# amplifier.net
KiCad netlist of a schematic drawn in EAGLE
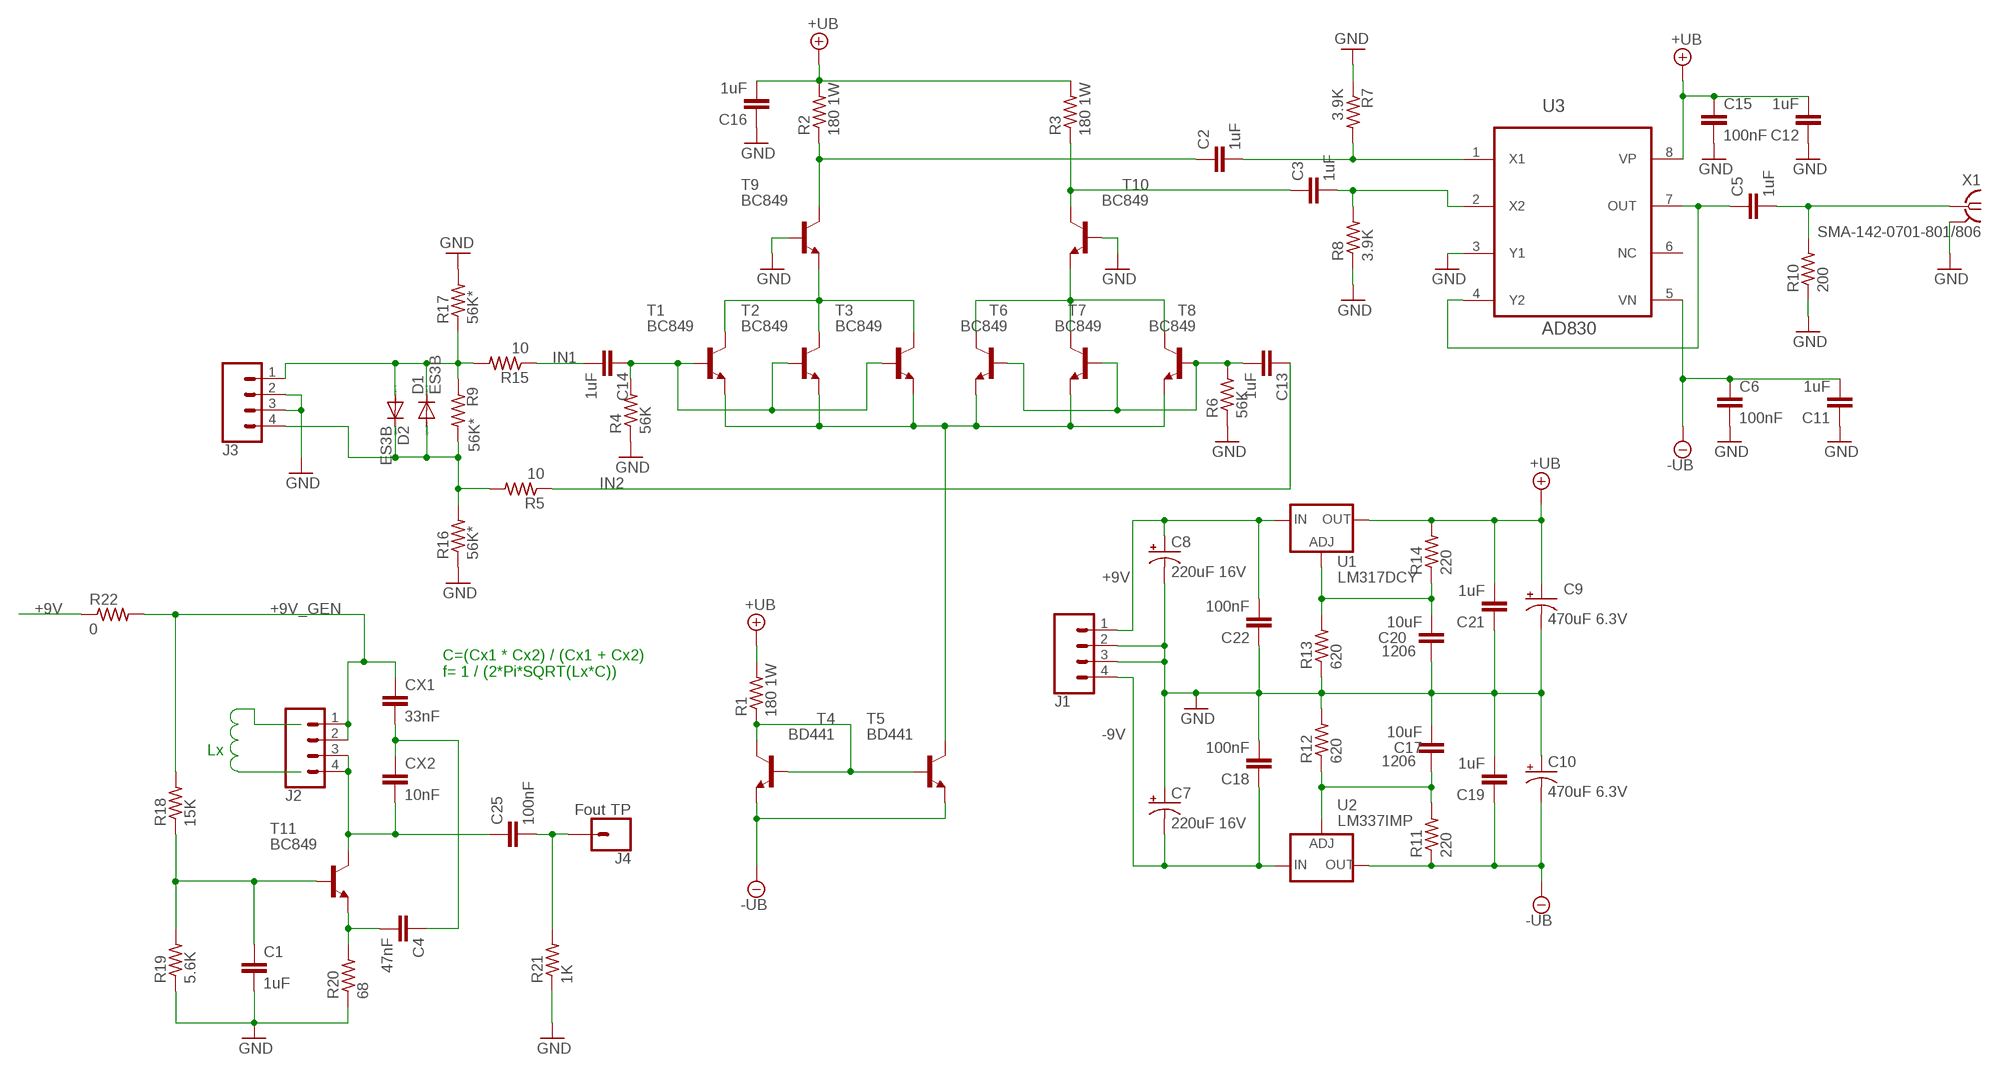
[diagram p0: schematic, sheet 1]

(export (version "E")
  (design (tool "Eeschema 10.0.6"))
  (components
    (comp (ref "C1")
      (value "1uF")
      (footprint "eagle-import:C0805")
      (libsource (lib "eagle-import") (part "C-EUC0805"))
    )
    (comp (ref "C2")
      (value "1uF")
      (footprint "eagle-import:C0805")
      (libsource (lib "eagle-import") (part "C-EUC0805"))
    )
    (comp (ref "C3")
      (value "1uF")
      (footprint "eagle-import:C0805")
      (libsource (lib "eagle-import") (part "C-EUC0805"))
    )
    (comp (ref "C4")
      (value "47nF")
      (footprint "eagle-import:C0805")
      (libsource (lib "eagle-import") (part "C-EUC0805"))
    )
    (comp (ref "C5")
      (value "1uF")
      (footprint "eagle-import:C0805")
      (libsource (lib "eagle-import") (part "C-EUC0805"))
    )
    (comp (ref "C6")
      (value "100nF")
      (footprint "eagle-import:C0805")
      (libsource (lib "eagle-import") (part "C-EUC0805"))
    )
    (comp (ref "C7")
      (value "220uF 16V")
      (footprint "eagle-import:153CLV-1010")
      (libsource (lib "eagle-import") (part "CPOL-US153CLV-1010"))
    )
    (comp (ref "C8")
      (value "220uF 16V")
      (footprint "eagle-import:153CLV-1010")
      (libsource (lib "eagle-import") (part "CPOL-US153CLV-1010"))
    )
    (comp (ref "C9")
      (value "470uF 6.3V")
      (footprint "eagle-import:153CLV-1010")
      (libsource (lib "eagle-import") (part "CPOL-US153CLV-1010"))
    )
    (comp (ref "C10")
      (value "470uF 6.3V")
      (footprint "eagle-import:153CLV-1010")
      (libsource (lib "eagle-import") (part "CPOL-US153CLV-1010"))
    )
    (comp (ref "C11")
      (value "1uF")
      (footprint "eagle-import:C0805")
      (libsource (lib "eagle-import") (part "C-EUC0805"))
    )
    (comp (ref "C12")
      (value "1uF")
      (footprint "eagle-import:C0805")
      (libsource (lib "eagle-import") (part "C-EUC0805"))
    )
    (comp (ref "C13")
      (value "1uF")
      (footprint "eagle-import:C0805")
      (libsource (lib "eagle-import") (part "C-EUC0805"))
    )
    (comp (ref "C14")
      (value "1uF")
      (footprint "eagle-import:C0805")
      (libsource (lib "eagle-import") (part "C-EUC0805"))
    )
    (comp (ref "C15")
      (value "100nF")
      (footprint "eagle-import:C0805")
      (libsource (lib "eagle-import") (part "C-EUC0805"))
    )
    (comp (ref "C16")
      (value "1uF")
      (footprint "eagle-import:C0805")
      (libsource (lib "eagle-import") (part "C-EUC0805"))
    )
    (comp (ref "C17")
      (value "10uF")
      (footprint "eagle-import:C1206")
      (fields (field (name "PACKAGE") "1206"))
      (libsource (lib "eagle-import") (part "C-EUC1206"))
    )
    (comp (ref "C18")
      (value "100nF")
      (footprint "eagle-import:C0805")
      (libsource (lib "eagle-import") (part "C-EUC0805"))
    )
    (comp (ref "C19")
      (value "1uF")
      (footprint "eagle-import:C0805")
      (libsource (lib "eagle-import") (part "C-EUC0805"))
    )
    (comp (ref "C20")
      (value "10uF")
      (footprint "eagle-import:C1206")
      (fields (field (name "PACKAGE") "1206"))
      (libsource (lib "eagle-import") (part "C-EUC1206"))
    )
    (comp (ref "C21")
      (value "1uF")
      (footprint "eagle-import:C0805")
      (libsource (lib "eagle-import") (part "C-EUC0805"))
    )
    (comp (ref "C22")
      (value "100nF")
      (footprint "eagle-import:C0805")
      (libsource (lib "eagle-import") (part "C-EUC0805"))
    )
    (comp (ref "C25")
      (value "100nF")
      (footprint "eagle-import:C0805")
      (libsource (lib "eagle-import") (part "C-EUC0805"))
    )
    (comp (ref "CX1")
      (value "33nF")
      (footprint "eagle-import:C0805")
      (libsource (lib "eagle-import") (part "C-EUC0805"))
    )
    (comp (ref "CX2")
      (value "10nF")
      (footprint "eagle-import:C0805")
      (libsource (lib "eagle-import") (part "C-EUC0805"))
    )
    (comp (ref "D1")
      (value "ES3B")
      (footprint "eagle-import:SMC")
      (libsource (lib "eagle-import") (part "DIODE-SMC"))
    )
    (comp (ref "D2")
      (value "ES3B")
      (footprint "eagle-import:SMC")
      (libsource (lib "eagle-import") (part "DIODE-SMC"))
    )
    (comp (ref "J1")
      (value "CONN_04LONGPADS")
      (footprint "eagle-import:1X04_LONGPADS")
      (libsource (lib "eagle-import") (part "CONN_04LONGPADS"))
    )
    (comp (ref "J2")
      (value "CONN_04LONGPADS")
      (footprint "eagle-import:1X04_LONGPADS")
      (libsource (lib "eagle-import") (part "CONN_04LONGPADS"))
    )
    (comp (ref "J3")
      (value "CONN_04LONGPADS")
      (footprint "eagle-import:1X04_LONGPADS")
      (libsource (lib "eagle-import") (part "CONN_04LONGPADS"))
    )
    (comp (ref "J4")
      (value "Fout TP")
      (footprint "eagle-import:SNAP-MALE")
      (libsource (lib "eagle-import") (part "CONN_01SNAP-MALE"))
    )
    (comp (ref "R1")
      (value "180 1W")
      (footprint "eagle-import:R1206W")
      (libsource (lib "eagle-import") (part "R-US_R1206W"))
    )
    (comp (ref "R2")
      (value "180 1W")
      (footprint "eagle-import:R1206W")
      (libsource (lib "eagle-import") (part "R-US_R1206W"))
    )
    (comp (ref "R3")
      (value "180 1W")
      (footprint "eagle-import:R1206W")
      (libsource (lib "eagle-import") (part "R-US_R1206W"))
    )
    (comp (ref "R4")
      (value "56K")
      (footprint "eagle-import:R1206W")
      (libsource (lib "eagle-import") (part "R-US_R1206W"))
    )
    (comp (ref "R5")
      (value "10")
      (footprint "eagle-import:R1206W")
      (libsource (lib "eagle-import") (part "R-US_R1206W"))
    )
    (comp (ref "R6")
      (value "56K")
      (footprint "eagle-import:R1206W")
      (libsource (lib "eagle-import") (part "R-US_R1206W"))
    )
    (comp (ref "R7")
      (value "3.9K")
      (footprint "eagle-import:R1206W")
      (libsource (lib "eagle-import") (part "R-US_R1206W"))
    )
    (comp (ref "R8")
      (value "3.9K")
      (footprint "eagle-import:R1206W")
      (libsource (lib "eagle-import") (part "R-US_R1206W"))
    )
    (comp (ref "R9")
      (value "56K*")
      (footprint "eagle-import:R1206W")
      (libsource (lib "eagle-import") (part "R-US_R1206W"))
    )
    (comp (ref "R10")
      (value "200")
      (footprint "eagle-import:R1206W")
      (libsource (lib "eagle-import") (part "R-US_R1206W"))
    )
    (comp (ref "R11")
      (value "220")
      (footprint "eagle-import:R1206W")
      (libsource (lib "eagle-import") (part "R-US_R1206W"))
    )
    (comp (ref "R12")
      (value "620")
      (footprint "eagle-import:R1206W")
      (libsource (lib "eagle-import") (part "R-US_R1206W"))
    )
    (comp (ref "R13")
      (value "620")
      (footprint "eagle-import:R1206W")
      (libsource (lib "eagle-import") (part "R-US_R1206W"))
    )
    (comp (ref "R14")
      (value "220")
      (footprint "eagle-import:R1206W")
      (libsource (lib "eagle-import") (part "R-US_R1206W"))
    )
    (comp (ref "R15")
      (value "10")
      (footprint "eagle-import:R1206W")
      (libsource (lib "eagle-import") (part "R-US_R1206W"))
    )
    (comp (ref "R16")
      (value "56K*")
      (footprint "eagle-import:R1206W")
      (libsource (lib "eagle-import") (part "R-US_R1206W"))
    )
    (comp (ref "R17")
      (value "56K*")
      (footprint "eagle-import:R1206W")
      (libsource (lib "eagle-import") (part "R-US_R1206W"))
    )
    (comp (ref "R18")
      (value "15K")
      (footprint "eagle-import:R1206W")
      (libsource (lib "eagle-import") (part "R-US_R1206W"))
    )
    (comp (ref "R19")
      (value "5.6K")
      (footprint "eagle-import:R1206W")
      (libsource (lib "eagle-import") (part "R-US_R1206W"))
    )
    (comp (ref "R20")
      (value "68")
      (footprint "eagle-import:R1206W")
      (libsource (lib "eagle-import") (part "R-US_R1206W"))
    )
    (comp (ref "R21")
      (value "1K")
      (footprint "eagle-import:R1206W")
      (libsource (lib "eagle-import") (part "R-US_R1206W"))
    )
    (comp (ref "R22")
      (value "0")
      (footprint "eagle-import:R1206W")
      (libsource (lib "eagle-import") (part "R-US_R1206W"))
    )
    (comp (ref "T1")
      (value "BC849")
      (footprint "eagle-import:SOT23")
      (libsource (lib "eagle-import") (part "BC849"))
    )
    (comp (ref "T2")
      (value "BC849")
      (footprint "eagle-import:SOT23")
      (libsource (lib "eagle-import") (part "BC849"))
    )
    (comp (ref "T3")
      (value "BC849")
      (footprint "eagle-import:SOT23")
      (libsource (lib "eagle-import") (part "BC849"))
    )
    (comp (ref "T4")
      (value "BD441")
      (footprint "eagle-import:TO126")
      (libsource (lib "eagle-import") (part "-NPN-TO126"))
    )
    (comp (ref "T5")
      (value "BD441")
      (footprint "eagle-import:TO126")
      (libsource (lib "eagle-import") (part "-NPN-TO126"))
    )
    (comp (ref "T6")
      (value "BC849")
      (footprint "eagle-import:SOT23")
      (libsource (lib "eagle-import") (part "BC849"))
    )
    (comp (ref "T7")
      (value "BC849")
      (footprint "eagle-import:SOT23")
      (libsource (lib "eagle-import") (part "BC849"))
    )
    (comp (ref "T8")
      (value "BC849")
      (footprint "eagle-import:SOT23")
      (libsource (lib "eagle-import") (part "BC849"))
    )
    (comp (ref "T9")
      (value "BC849")
      (footprint "eagle-import:SOT23")
      (libsource (lib "eagle-import") (part "BC849"))
    )
    (comp (ref "T10")
      (value "BC849")
      (footprint "eagle-import:SOT23")
      (libsource (lib "eagle-import") (part "BC849"))
    )
    (comp (ref "T11")
      (value "BC849")
      (footprint "eagle-import:SOT23")
      (libsource (lib "eagle-import") (part "BC849"))
    )
    (comp (ref "U1")
      (value "LM317DCY")
      (footprint "eagle-import:SOT223")
      (libsource (lib "eagle-import") (part "LM317DCY"))
    )
    (comp (ref "U2")
      (value "LM337IMP")
      (footprint "eagle-import:SOT223")
      (libsource (lib "eagle-import") (part "LM337IMP"))
    )
    (comp (ref "U3")
      (value "AD830")
      (footprint "eagle-import:SOIC127P600X175-8N")
      (libsource (lib "eagle-import") (part "AD830"))
    )
    (comp (ref "X1")
      (value "SMA-142-0701-801/806")
      (footprint "eagle-import:J502-ND-142-0701-801_806")
      (fields (field (name "MF") "JOHNSON COMPONENTS") (field (name "MPN") "142-0701-801"))
      (libsource (lib "eagle-import") (part "SMA-142-0701-801/806"))
    )
  )
  (nets
    (net (code "1") (name "+UB") (class "Default")
      (node (ref "C12") (pin "2") (pinfunction "2_2") (pintype "passive"))
      (node (ref "C15") (pin "1") (pinfunction "1_1") (pintype "passive"))
      (node (ref "C16") (pin "2") (pinfunction "2_2") (pintype "passive"))
      (node (ref "C21") (pin "2") (pinfunction "2_2") (pintype "passive"))
      (node (ref "C9") (pin "+") (pinfunction "+_+") (pintype "passive"))
      (node (ref "R1") (pin "2") (pinfunction "2_2") (pintype "passive"))
      (node (ref "R14") (pin "2") (pinfunction "2_2") (pintype "passive"))
      (node (ref "R2") (pin "2") (pinfunction "2_2") (pintype "passive"))
      (node (ref "R3") (pin "2") (pinfunction "2_2") (pintype "passive"))
      (node (ref "U1") (pin "2") (pinfunction "OUT_2") (pintype "passive"))
      (node (ref "U1") (pin "4") (pinfunction "OUT_4") (pintype "passive"))
      (node (ref "U3") (pin "8") (pinfunction "VP_8") (pintype "power_in"))
    )
    (net (code "2") (name "-UB") (class "Default")
      (node (ref "C10") (pin "-") (pinfunction "-_-") (pintype "passive"))
      (node (ref "C11") (pin "2") (pinfunction "2_2") (pintype "passive"))
      (node (ref "C19") (pin "1") (pinfunction "1_1") (pintype "passive"))
      (node (ref "C6") (pin "1") (pinfunction "1_1") (pintype "passive"))
      (node (ref "R11") (pin "1") (pinfunction "1_1") (pintype "passive"))
      (node (ref "T4") (pin "1") (pinfunction "E_1") (pintype "passive"))
      (node (ref "T5") (pin "1") (pinfunction "E_1") (pintype "passive"))
      (node (ref "U2") (pin "3") (pinfunction "OUT_3") (pintype "passive"))
      (node (ref "U3") (pin "5") (pinfunction "VN_5") (pintype "power_in"))
    )
    (net (code "3") (name "/+9V") (class "Default")
      (node (ref "C22") (pin "2") (pinfunction "2_2") (pintype "passive"))
      (node (ref "C8") (pin "+") (pinfunction "+_+") (pintype "passive"))
      (node (ref "J1") (pin "1") (pinfunction "1_1") (pintype "passive"))
      (node (ref "R22") (pin "1") (pinfunction "1_1") (pintype "passive"))
      (node (ref "U1") (pin "3") (pinfunction "IN_3") (pintype "input"))
    )
    (net (code "4") (name "/+9V_GEN") (class "Default")
      (node (ref "CX1") (pin "1") (pinfunction "1_1") (pintype "passive"))
      (node (ref "J2") (pin "1") (pinfunction "1_1") (pintype "passive"))
      (node (ref "J2") (pin "2") (pinfunction "2_2") (pintype "passive"))
      (node (ref "R18") (pin "2") (pinfunction "2_2") (pintype "passive"))
      (node (ref "R22") (pin "2") (pinfunction "2_2") (pintype "passive"))
    )
    (net (code "5") (name "/-9V") (class "Default")
      (node (ref "C18") (pin "1") (pinfunction "1_1") (pintype "passive"))
      (node (ref "C7") (pin "-") (pinfunction "-_-") (pintype "passive"))
      (node (ref "J1") (pin "4") (pinfunction "4_4") (pintype "passive"))
      (node (ref "U2") (pin "2") (pinfunction "IN_2") (pintype "input"))
      (node (ref "U2") (pin "4") (pinfunction "IN_4") (pintype "input"))
    )
    (net (code "6") (name "/IN1") (class "Default")
      (node (ref "C14") (pin "2") (pinfunction "2_2") (pintype "passive"))
      (node (ref "R15") (pin "1") (pinfunction "1_1") (pintype "passive"))
    )
    (net (code "7") (name "/IN2") (class "Default")
      (node (ref "C13") (pin "1") (pinfunction "1_1") (pintype "passive"))
      (node (ref "R5") (pin "1") (pinfunction "1_1") (pintype "passive"))
    )
    (net (code "8") (name "/NC") (class "Default")
      (node (ref "U3") (pin "6") (pinfunction "NC_6") (pintype "power_in"))
    )
    (net (code "9") (name "GND") (class "Default")
      (node (ref "C1") (pin "2") (pinfunction "2_2") (pintype "passive"))
      (node (ref "C10") (pin "+") (pinfunction "+_+") (pintype "passive"))
      (node (ref "C11") (pin "1") (pinfunction "1_1") (pintype "passive"))
      (node (ref "C12") (pin "1") (pinfunction "1_1") (pintype "passive"))
      (node (ref "C15") (pin "2") (pinfunction "2_2") (pintype "passive"))
      (node (ref "C16") (pin "1") (pinfunction "1_1") (pintype "passive"))
      (node (ref "C17") (pin "2") (pinfunction "2_2") (pintype "passive"))
      (node (ref "C18") (pin "2") (pinfunction "2_2") (pintype "passive"))
      (node (ref "C19") (pin "2") (pinfunction "2_2") (pintype "passive"))
      (node (ref "C20") (pin "1") (pinfunction "1_1") (pintype "passive"))
      (node (ref "C21") (pin "1") (pinfunction "1_1") (pintype "passive"))
      (node (ref "C22") (pin "1") (pinfunction "1_1") (pintype "passive"))
      (node (ref "C6") (pin "2") (pinfunction "2_2") (pintype "passive"))
      (node (ref "C7") (pin "+") (pinfunction "+_+") (pintype "passive"))
      (node (ref "C8") (pin "-") (pinfunction "-_-") (pintype "passive"))
      (node (ref "C9") (pin "-") (pinfunction "-_-") (pintype "passive"))
      (node (ref "J1") (pin "2") (pinfunction "2_2") (pintype "passive"))
      (node (ref "J1") (pin "3") (pinfunction "3_3") (pintype "passive"))
      (node (ref "J3") (pin "2") (pinfunction "2_2") (pintype "passive"))
      (node (ref "J3") (pin "3") (pinfunction "3_3") (pintype "passive"))
      (node (ref "R10") (pin "1") (pinfunction "1_1") (pintype "passive"))
      (node (ref "R12") (pin "2") (pinfunction "2_2") (pintype "passive"))
      (node (ref "R13") (pin "1") (pinfunction "1_1") (pintype "passive"))
      (node (ref "R16") (pin "1") (pinfunction "1_1") (pintype "passive"))
      (node (ref "R17") (pin "2") (pinfunction "2_2") (pintype "passive"))
      (node (ref "R19") (pin "1") (pinfunction "1_1") (pintype "passive"))
      (node (ref "R20") (pin "1") (pinfunction "1_1") (pintype "passive"))
      (node (ref "R21") (pin "1") (pinfunction "1_1") (pintype "passive"))
      (node (ref "R4") (pin "1") (pinfunction "1_1") (pintype "passive"))
      (node (ref "R6") (pin "1") (pinfunction "1_1") (pintype "passive"))
      (node (ref "R7") (pin "1") (pinfunction "1_1") (pintype "passive"))
      (node (ref "R8") (pin "1") (pinfunction "1_1") (pintype "passive"))
      (node (ref "T10") (pin "1") (pinfunction "B_1") (pintype "passive"))
      (node (ref "T9") (pin "1") (pinfunction "B_1") (pintype "passive"))
      (node (ref "U3") (pin "3") (pinfunction "Y1_3") (pintype "input"))
      (node (ref "X1") (pin "G@1") (pinfunction "2_G@1") (pintype "passive"))
      (node (ref "X1") (pin "G@2") (pinfunction "2_G@2") (pintype "passive"))
      (node (ref "X1") (pin "G@3") (pinfunction "2_G@3") (pintype "passive"))
      (node (ref "X1") (pin "G@4") (pinfunction "2_G@4") (pintype "passive"))
    )
    (net (code "10") (name "Net-(C4-Pad1)") (class "Default")
      (node (ref "C4") (pin "1") (pinfunction "1_1") (pintype "passive"))
      (node (ref "CX1") (pin "2") (pinfunction "2_2") (pintype "passive"))
      (node (ref "CX2") (pin "1") (pinfunction "1_1") (pintype "passive"))
    )
    (net (code "11") (name "Net-(C5-Pad2)") (class "Default")
      (node (ref "C5") (pin "2") (pinfunction "2_2") (pintype "passive"))
      (node (ref "R10") (pin "2") (pinfunction "2_2") (pintype "passive"))
      (node (ref "X1") (pin "1") (pinfunction "1_1") (pintype "passive"))
    )
    (net (code "12") (name "Net-(D1-PadA)") (class "Default")
      (node (ref "D1") (pin "A") (pinfunction "A_A") (pintype "passive"))
      (node (ref "D2") (pin "C") (pinfunction "C_C") (pintype "passive"))
      (node (ref "J3") (pin "4") (pinfunction "4_4") (pintype "passive"))
      (node (ref "R16") (pin "2") (pinfunction "2_2") (pintype "passive"))
      (node (ref "R5") (pin "2") (pinfunction "2_2") (pintype "passive"))
      (node (ref "R9") (pin "2") (pinfunction "2_2") (pintype "passive"))
    )
    (net (code "13") (name "Net-(D1-PadC)") (class "Default")
      (node (ref "D1") (pin "C") (pinfunction "C_C") (pintype "passive"))
      (node (ref "D2") (pin "A") (pinfunction "A_A") (pintype "passive"))
      (node (ref "J3") (pin "1") (pinfunction "1_1") (pintype "passive"))
      (node (ref "R15") (pin "2") (pinfunction "2_2") (pintype "passive"))
      (node (ref "R17") (pin "1") (pinfunction "1_1") (pintype "passive"))
      (node (ref "R9") (pin "1") (pinfunction "1_1") (pintype "passive"))
    )
    (net (code "14") (name "Net-(J4-1)") (class "Default")
      (node (ref "C25") (pin "2") (pinfunction "2_2") (pintype "passive"))
      (node (ref "J4") (pin "2") (pinfunction "1_2") (pintype "passive"))
      (node (ref "R21") (pin "2") (pinfunction "2_2") (pintype "passive"))
    )
    (net (code "15") (name "Net-(T1-B)") (class "Default")
      (node (ref "C14") (pin "1") (pinfunction "1_1") (pintype "passive"))
      (node (ref "R4") (pin "2") (pinfunction "2_2") (pintype "passive"))
      (node (ref "T1") (pin "1") (pinfunction "B_1") (pintype "passive"))
      (node (ref "T2") (pin "1") (pinfunction "B_1") (pintype "passive"))
      (node (ref "T3") (pin "1") (pinfunction "B_1") (pintype "passive"))
    )
    (net (code "16") (name "Net-(T1-C)") (class "Default")
      (node (ref "T1") (pin "3") (pinfunction "C_3") (pintype "passive"))
      (node (ref "T2") (pin "3") (pinfunction "C_3") (pintype "passive"))
      (node (ref "T3") (pin "3") (pinfunction "C_3") (pintype "passive"))
      (node (ref "T9") (pin "2") (pinfunction "E_2") (pintype "passive"))
    )
    (net (code "17") (name "Net-(T1-E)") (class "Default")
      (node (ref "T1") (pin "2") (pinfunction "E_2") (pintype "passive"))
      (node (ref "T2") (pin "2") (pinfunction "E_2") (pintype "passive"))
      (node (ref "T3") (pin "2") (pinfunction "E_2") (pintype "passive"))
      (node (ref "T5") (pin "2") (pinfunction "C_2") (pintype "passive"))
      (node (ref "T6") (pin "2") (pinfunction "E_2") (pintype "passive"))
      (node (ref "T7") (pin "2") (pinfunction "E_2") (pintype "passive"))
      (node (ref "T8") (pin "2") (pinfunction "E_2") (pintype "passive"))
    )
    (net (code "18") (name "Net-(T4-B)") (class "Default")
      (node (ref "R1") (pin "1") (pinfunction "1_1") (pintype "passive"))
      (node (ref "T4") (pin "2") (pinfunction "C_2") (pintype "passive"))
      (node (ref "T4") (pin "3") (pinfunction "B_3") (pintype "passive"))
      (node (ref "T5") (pin "3") (pinfunction "B_3") (pintype "passive"))
    )
    (net (code "19") (name "Net-(T6-B)") (class "Default")
      (node (ref "C13") (pin "2") (pinfunction "2_2") (pintype "passive"))
      (node (ref "R6") (pin "2") (pinfunction "2_2") (pintype "passive"))
      (node (ref "T6") (pin "1") (pinfunction "B_1") (pintype "passive"))
      (node (ref "T7") (pin "1") (pinfunction "B_1") (pintype "passive"))
      (node (ref "T8") (pin "1") (pinfunction "B_1") (pintype "passive"))
    )
    (net (code "20") (name "Net-(T9-C)") (class "Default")
      (node (ref "C2") (pin "1") (pinfunction "1_1") (pintype "passive"))
      (node (ref "R2") (pin "1") (pinfunction "1_1") (pintype "passive"))
      (node (ref "T9") (pin "3") (pinfunction "C_3") (pintype "passive"))
    )
    (net (code "21") (name "Net-(T10-C)") (class "Default")
      (node (ref "C3") (pin "1") (pinfunction "1_1") (pintype "passive"))
      (node (ref "R3") (pin "1") (pinfunction "1_1") (pintype "passive"))
      (node (ref "T10") (pin "3") (pinfunction "C_3") (pintype "passive"))
    )
    (net (code "22") (name "Net-(T10-E)") (class "Default")
      (node (ref "T10") (pin "2") (pinfunction "E_2") (pintype "passive"))
      (node (ref "T6") (pin "3") (pinfunction "C_3") (pintype "passive"))
      (node (ref "T7") (pin "3") (pinfunction "C_3") (pintype "passive"))
      (node (ref "T8") (pin "3") (pinfunction "C_3") (pintype "passive"))
    )
    (net (code "23") (name "Net-(T11-B)") (class "Default")
      (node (ref "C1") (pin "1") (pinfunction "1_1") (pintype "passive"))
      (node (ref "R18") (pin "1") (pinfunction "1_1") (pintype "passive"))
      (node (ref "R19") (pin "2") (pinfunction "2_2") (pintype "passive"))
      (node (ref "T11") (pin "1") (pinfunction "B_1") (pintype "passive"))
    )
    (net (code "24") (name "Net-(T11-C)") (class "Default")
      (node (ref "C25") (pin "1") (pinfunction "1_1") (pintype "passive"))
      (node (ref "CX2") (pin "2") (pinfunction "2_2") (pintype "passive"))
      (node (ref "J2") (pin "3") (pinfunction "3_3") (pintype "passive"))
      (node (ref "J2") (pin "4") (pinfunction "4_4") (pintype "passive"))
      (node (ref "T11") (pin "3") (pinfunction "C_3") (pintype "passive"))
    )
    (net (code "25") (name "Net-(T11-E)") (class "Default")
      (node (ref "C4") (pin "2") (pinfunction "2_2") (pintype "passive"))
      (node (ref "R20") (pin "2") (pinfunction "2_2") (pintype "passive"))
      (node (ref "T11") (pin "2") (pinfunction "E_2") (pintype "passive"))
    )
    (net (code "26") (name "Net-(U1-ADJ)") (class "Default")
      (node (ref "C20") (pin "2") (pinfunction "2_2") (pintype "passive"))
      (node (ref "R13") (pin "2") (pinfunction "2_2") (pintype "passive"))
      (node (ref "R14") (pin "1") (pinfunction "1_1") (pintype "passive"))
      (node (ref "U1") (pin "1") (pinfunction "ADJ_1") (pintype "input"))
    )
    (net (code "27") (name "Net-(U2-ADJ)") (class "Default")
      (node (ref "C17") (pin "1") (pinfunction "1_1") (pintype "passive"))
      (node (ref "R11") (pin "2") (pinfunction "2_2") (pintype "passive"))
      (node (ref "R12") (pin "1") (pinfunction "1_1") (pintype "passive"))
      (node (ref "U2") (pin "1") (pinfunction "ADJ_1") (pintype "input"))
    )
    (net (code "28") (name "Net-(U3-OUT)") (class "Default")
      (node (ref "C5") (pin "1") (pinfunction "1_1") (pintype "passive"))
      (node (ref "U3") (pin "4") (pinfunction "Y2_4") (pintype "input"))
      (node (ref "U3") (pin "7") (pinfunction "OUT_7") (pintype "output"))
    )
    (net (code "29") (name "Net-(U3-X1)") (class "Default")
      (node (ref "C2") (pin "2") (pinfunction "2_2") (pintype "passive"))
      (node (ref "R7") (pin "2") (pinfunction "2_2") (pintype "passive"))
      (node (ref "U3") (pin "1") (pinfunction "X1_1") (pintype "input"))
    )
    (net (code "30") (name "Net-(U3-X2)") (class "Default")
      (node (ref "C3") (pin "2") (pinfunction "2_2") (pintype "passive"))
      (node (ref "R8") (pin "2") (pinfunction "2_2") (pintype "passive"))
      (node (ref "U3") (pin "2") (pinfunction "X2_2") (pintype "input"))
    )
  )
)
